# BSU_Sensing.net
KiCad netlist of a schematic drawn in Altium Designer
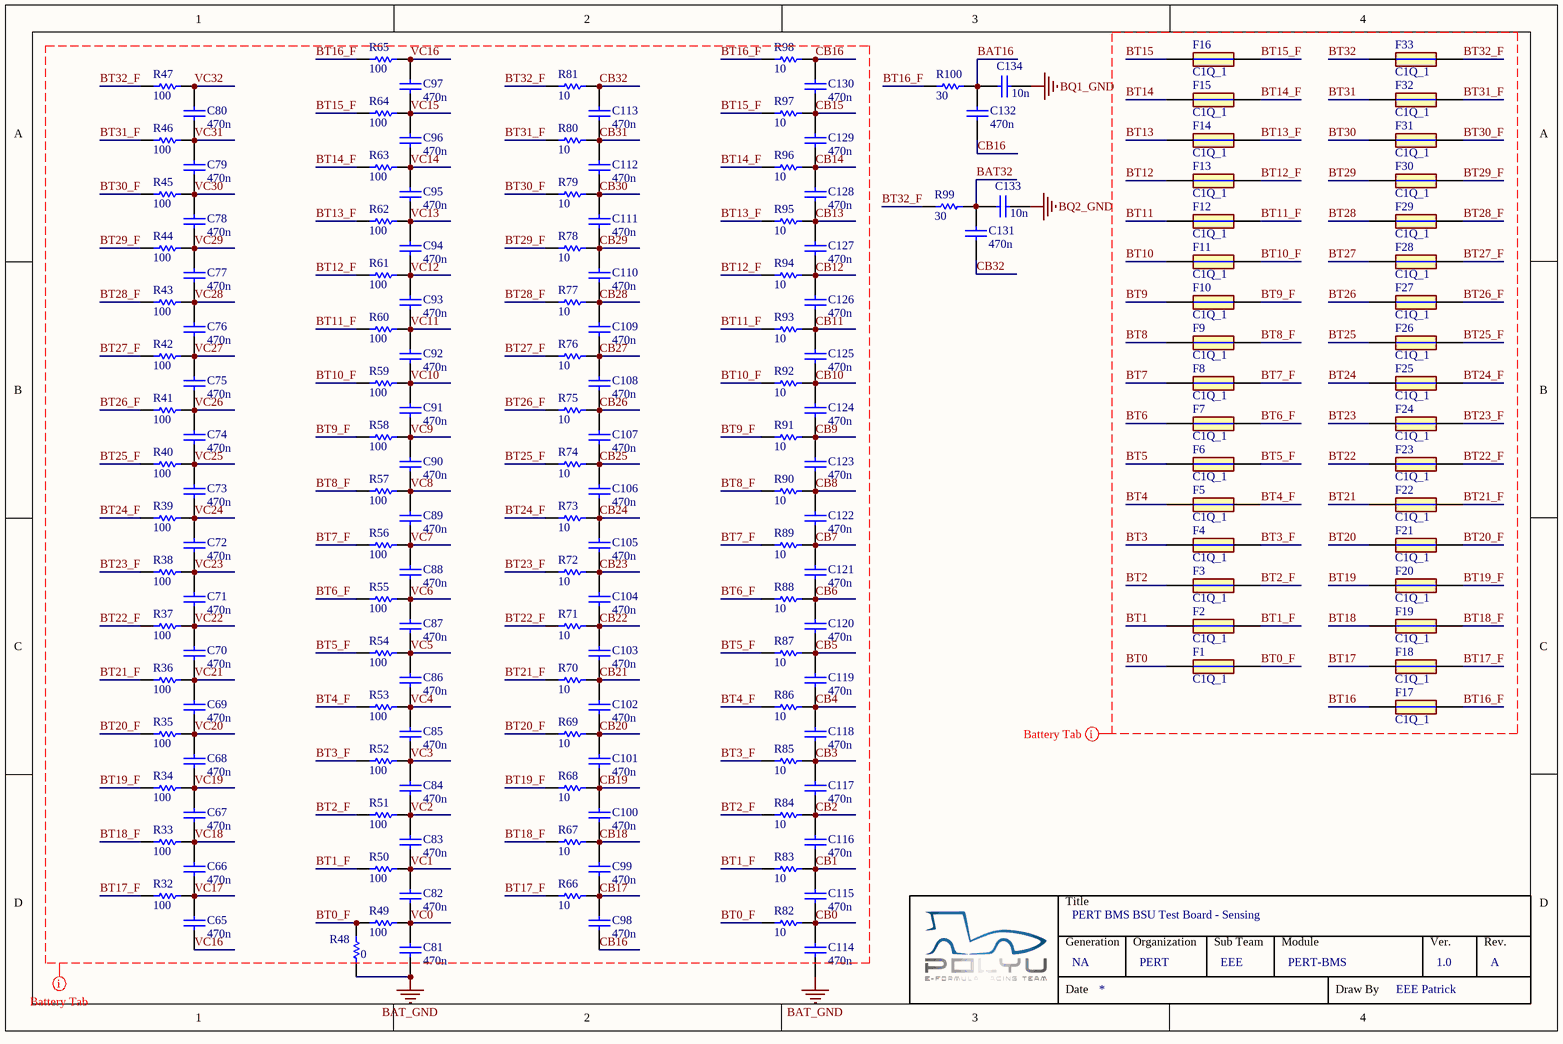
[diagram p0: BSU_Sensing.SchDoc]

(export (version "E")
  (design (tool "Eeschema 10.0.6"))
  (components
    (comp (ref "C65")
      (value "470n")
      (footprint "0603_SMD_C")
      (description "0603 SMD Capacitor")
      (libsource (lib "BMS_ShareComponentLibrary") (part "0603_SMD_Capacitor"))
    )
    (comp (ref "C66")
      (value "470n")
      (footprint "0603_SMD_C")
      (description "0603 SMD Capacitor")
      (libsource (lib "BMS_ShareComponentLibrary") (part "0603_SMD_Capacitor"))
    )
    (comp (ref "C67")
      (value "470n")
      (footprint "0603_SMD_C")
      (description "0603 SMD Capacitor")
      (libsource (lib "BMS_ShareComponentLibrary") (part "0603_SMD_Capacitor"))
    )
    (comp (ref "C68")
      (value "470n")
      (footprint "0603_SMD_C")
      (description "0603 SMD Capacitor")
      (libsource (lib "BMS_ShareComponentLibrary") (part "0603_SMD_Capacitor"))
    )
    (comp (ref "C69")
      (value "470n")
      (footprint "0603_SMD_C")
      (description "0603 SMD Capacitor")
      (libsource (lib "BMS_ShareComponentLibrary") (part "0603_SMD_Capacitor"))
    )
    (comp (ref "C70")
      (value "470n")
      (footprint "0603_SMD_C")
      (description "0603 SMD Capacitor")
      (libsource (lib "BMS_ShareComponentLibrary") (part "0603_SMD_Capacitor"))
    )
    (comp (ref "C71")
      (value "470n")
      (footprint "0603_SMD_C")
      (description "0603 SMD Capacitor")
      (libsource (lib "BMS_ShareComponentLibrary") (part "0603_SMD_Capacitor"))
    )
    (comp (ref "C72")
      (value "470n")
      (footprint "0603_SMD_C")
      (description "0603 SMD Capacitor")
      (libsource (lib "BMS_ShareComponentLibrary") (part "0603_SMD_Capacitor"))
    )
    (comp (ref "C73")
      (value "470n")
      (footprint "0603_SMD_C")
      (description "0603 SMD Capacitor")
      (libsource (lib "BMS_ShareComponentLibrary") (part "0603_SMD_Capacitor"))
    )
    (comp (ref "C74")
      (value "470n")
      (footprint "0603_SMD_C")
      (description "0603 SMD Capacitor")
      (libsource (lib "BMS_ShareComponentLibrary") (part "0603_SMD_Capacitor"))
    )
    (comp (ref "C75")
      (value "470n")
      (footprint "0603_SMD_C")
      (description "0603 SMD Capacitor")
      (libsource (lib "BMS_ShareComponentLibrary") (part "0603_SMD_Capacitor"))
    )
    (comp (ref "C76")
      (value "470n")
      (footprint "0603_SMD_C")
      (description "0603 SMD Capacitor")
      (libsource (lib "BMS_ShareComponentLibrary") (part "0603_SMD_Capacitor"))
    )
    (comp (ref "C77")
      (value "470n")
      (footprint "0603_SMD_C")
      (description "0603 SMD Capacitor")
      (libsource (lib "BMS_ShareComponentLibrary") (part "0603_SMD_Capacitor"))
    )
    (comp (ref "C78")
      (value "470n")
      (footprint "0603_SMD_C")
      (description "0603 SMD Capacitor")
      (libsource (lib "BMS_ShareComponentLibrary") (part "0603_SMD_Capacitor"))
    )
    (comp (ref "C79")
      (value "470n")
      (footprint "0603_SMD_C")
      (description "0603 SMD Capacitor")
      (libsource (lib "BMS_ShareComponentLibrary") (part "0603_SMD_Capacitor"))
    )
    (comp (ref "C80")
      (value "470n")
      (footprint "0603_SMD_C")
      (description "0603 SMD Capacitor")
      (libsource (lib "BMS_ShareComponentLibrary") (part "0603_SMD_Capacitor"))
    )
    (comp (ref "C81")
      (value "470n")
      (footprint "0603_SMD_C")
      (description "0603 SMD Capacitor")
      (libsource (lib "BMS_ShareComponentLibrary") (part "0603_SMD_Capacitor"))
    )
    (comp (ref "C82")
      (value "470n")
      (footprint "0603_SMD_C")
      (description "0603 SMD Capacitor")
      (libsource (lib "BMS_ShareComponentLibrary") (part "0603_SMD_Capacitor"))
    )
    (comp (ref "C83")
      (value "470n")
      (footprint "0603_SMD_C")
      (description "0603 SMD Capacitor")
      (libsource (lib "BMS_ShareComponentLibrary") (part "0603_SMD_Capacitor"))
    )
    (comp (ref "C84")
      (value "470n")
      (footprint "0603_SMD_C")
      (description "0603 SMD Capacitor")
      (libsource (lib "BMS_ShareComponentLibrary") (part "0603_SMD_Capacitor"))
    )
    (comp (ref "C85")
      (value "470n")
      (footprint "0603_SMD_C")
      (description "0603 SMD Capacitor")
      (libsource (lib "BMS_ShareComponentLibrary") (part "0603_SMD_Capacitor"))
    )
    (comp (ref "C86")
      (value "470n")
      (footprint "0603_SMD_C")
      (description "0603 SMD Capacitor")
      (libsource (lib "BMS_ShareComponentLibrary") (part "0603_SMD_Capacitor"))
    )
    (comp (ref "C87")
      (value "470n")
      (footprint "0603_SMD_C")
      (description "0603 SMD Capacitor")
      (libsource (lib "BMS_ShareComponentLibrary") (part "0603_SMD_Capacitor"))
    )
    (comp (ref "C88")
      (value "470n")
      (footprint "0603_SMD_C")
      (description "0603 SMD Capacitor")
      (libsource (lib "BMS_ShareComponentLibrary") (part "0603_SMD_Capacitor"))
    )
    (comp (ref "C89")
      (value "470n")
      (footprint "0603_SMD_C")
      (description "0603 SMD Capacitor")
      (libsource (lib "BMS_ShareComponentLibrary") (part "0603_SMD_Capacitor"))
    )
    (comp (ref "C90")
      (value "470n")
      (footprint "0603_SMD_C")
      (description "0603 SMD Capacitor")
      (libsource (lib "BMS_ShareComponentLibrary") (part "0603_SMD_Capacitor"))
    )
    (comp (ref "C91")
      (value "470n")
      (footprint "0603_SMD_C")
      (description "0603 SMD Capacitor")
      (libsource (lib "BMS_ShareComponentLibrary") (part "0603_SMD_Capacitor"))
    )
    (comp (ref "C92")
      (value "470n")
      (footprint "0603_SMD_C")
      (description "0603 SMD Capacitor")
      (libsource (lib "BMS_ShareComponentLibrary") (part "0603_SMD_Capacitor"))
    )
    (comp (ref "C93")
      (value "470n")
      (footprint "0603_SMD_C")
      (description "0603 SMD Capacitor")
      (libsource (lib "BMS_ShareComponentLibrary") (part "0603_SMD_Capacitor"))
    )
    (comp (ref "C94")
      (value "470n")
      (footprint "0603_SMD_C")
      (description "0603 SMD Capacitor")
      (libsource (lib "BMS_ShareComponentLibrary") (part "0603_SMD_Capacitor"))
    )
    (comp (ref "C95")
      (value "470n")
      (footprint "0603_SMD_C")
      (description "0603 SMD Capacitor")
      (libsource (lib "BMS_ShareComponentLibrary") (part "0603_SMD_Capacitor"))
    )
    (comp (ref "C96")
      (value "470n")
      (footprint "0603_SMD_C")
      (description "0603 SMD Capacitor")
      (libsource (lib "BMS_ShareComponentLibrary") (part "0603_SMD_Capacitor"))
    )
    (comp (ref "C97")
      (value "470n")
      (footprint "0603_SMD_C")
      (description "0603 SMD Capacitor")
      (libsource (lib "BMS_ShareComponentLibrary") (part "0603_SMD_Capacitor"))
    )
    (comp (ref "C98")
      (value "470n")
      (footprint "0603_SMD_C")
      (description "0603 SMD Capacitor")
      (libsource (lib "BMS_ShareComponentLibrary") (part "0603_SMD_Capacitor"))
    )
    (comp (ref "C99")
      (value "470n")
      (footprint "0603_SMD_C")
      (description "0603 SMD Capacitor")
      (libsource (lib "BMS_ShareComponentLibrary") (part "0603_SMD_Capacitor"))
    )
    (comp (ref "C100")
      (value "470n")
      (footprint "0603_SMD_C")
      (description "0603 SMD Capacitor")
      (libsource (lib "BMS_ShareComponentLibrary") (part "0603_SMD_Capacitor"))
    )
    (comp (ref "C101")
      (value "470n")
      (footprint "0603_SMD_C")
      (description "0603 SMD Capacitor")
      (libsource (lib "BMS_ShareComponentLibrary") (part "0603_SMD_Capacitor"))
    )
    (comp (ref "C102")
      (value "470n")
      (footprint "0603_SMD_C")
      (description "0603 SMD Capacitor")
      (libsource (lib "BMS_ShareComponentLibrary") (part "0603_SMD_Capacitor"))
    )
    (comp (ref "C103")
      (value "470n")
      (footprint "0603_SMD_C")
      (description "0603 SMD Capacitor")
      (libsource (lib "BMS_ShareComponentLibrary") (part "0603_SMD_Capacitor"))
    )
    (comp (ref "C104")
      (value "470n")
      (footprint "0603_SMD_C")
      (description "0603 SMD Capacitor")
      (libsource (lib "BMS_ShareComponentLibrary") (part "0603_SMD_Capacitor"))
    )
    (comp (ref "C105")
      (value "470n")
      (footprint "0603_SMD_C")
      (description "0603 SMD Capacitor")
      (libsource (lib "BMS_ShareComponentLibrary") (part "0603_SMD_Capacitor"))
    )
    (comp (ref "C106")
      (value "470n")
      (footprint "0603_SMD_C")
      (description "0603 SMD Capacitor")
      (libsource (lib "BMS_ShareComponentLibrary") (part "0603_SMD_Capacitor"))
    )
    (comp (ref "C107")
      (value "470n")
      (footprint "0603_SMD_C")
      (description "0603 SMD Capacitor")
      (libsource (lib "BMS_ShareComponentLibrary") (part "0603_SMD_Capacitor"))
    )
    (comp (ref "C108")
      (value "470n")
      (footprint "0603_SMD_C")
      (description "0603 SMD Capacitor")
      (libsource (lib "BMS_ShareComponentLibrary") (part "0603_SMD_Capacitor"))
    )
    (comp (ref "C109")
      (value "470n")
      (footprint "0603_SMD_C")
      (description "0603 SMD Capacitor")
      (libsource (lib "BMS_ShareComponentLibrary") (part "0603_SMD_Capacitor"))
    )
    (comp (ref "C110")
      (value "470n")
      (footprint "0603_SMD_C")
      (description "0603 SMD Capacitor")
      (libsource (lib "BMS_ShareComponentLibrary") (part "0603_SMD_Capacitor"))
    )
    (comp (ref "C111")
      (value "470n")
      (footprint "0603_SMD_C")
      (description "0603 SMD Capacitor")
      (libsource (lib "BMS_ShareComponentLibrary") (part "0603_SMD_Capacitor"))
    )
    (comp (ref "C112")
      (value "470n")
      (footprint "0603_SMD_C")
      (description "0603 SMD Capacitor")
      (libsource (lib "BMS_ShareComponentLibrary") (part "0603_SMD_Capacitor"))
    )
    (comp (ref "C113")
      (value "470n")
      (footprint "0603_SMD_C")
      (description "0603 SMD Capacitor")
      (libsource (lib "BMS_ShareComponentLibrary") (part "0603_SMD_Capacitor"))
    )
    (comp (ref "C114")
      (value "470n")
      (footprint "0603_SMD_C")
      (description "0603 SMD Capacitor")
      (libsource (lib "BMS_ShareComponentLibrary") (part "0603_SMD_Capacitor"))
    )
    (comp (ref "C115")
      (value "470n")
      (footprint "0603_SMD_C")
      (description "0603 SMD Capacitor")
      (libsource (lib "BMS_ShareComponentLibrary") (part "0603_SMD_Capacitor"))
    )
    (comp (ref "C116")
      (value "470n")
      (footprint "0603_SMD_C")
      (description "0603 SMD Capacitor")
      (libsource (lib "BMS_ShareComponentLibrary") (part "0603_SMD_Capacitor"))
    )
    (comp (ref "C117")
      (value "470n")
      (footprint "0603_SMD_C")
      (description "0603 SMD Capacitor")
      (libsource (lib "BMS_ShareComponentLibrary") (part "0603_SMD_Capacitor"))
    )
    (comp (ref "C118")
      (value "470n")
      (footprint "0603_SMD_C")
      (description "0603 SMD Capacitor")
      (libsource (lib "BMS_ShareComponentLibrary") (part "0603_SMD_Capacitor"))
    )
    (comp (ref "C119")
      (value "470n")
      (footprint "0603_SMD_C")
      (description "0603 SMD Capacitor")
      (libsource (lib "BMS_ShareComponentLibrary") (part "0603_SMD_Capacitor"))
    )
    (comp (ref "C120")
      (value "470n")
      (footprint "0603_SMD_C")
      (description "0603 SMD Capacitor")
      (libsource (lib "BMS_ShareComponentLibrary") (part "0603_SMD_Capacitor"))
    )
    (comp (ref "C121")
      (value "470n")
      (footprint "0603_SMD_C")
      (description "0603 SMD Capacitor")
      (libsource (lib "BMS_ShareComponentLibrary") (part "0603_SMD_Capacitor"))
    )
    (comp (ref "C122")
      (value "470n")
      (footprint "0603_SMD_C")
      (description "0603 SMD Capacitor")
      (libsource (lib "BMS_ShareComponentLibrary") (part "0603_SMD_Capacitor"))
    )
    (comp (ref "C123")
      (value "470n")
      (footprint "0603_SMD_C")
      (description "0603 SMD Capacitor")
      (libsource (lib "BMS_ShareComponentLibrary") (part "0603_SMD_Capacitor"))
    )
    (comp (ref "C124")
      (value "470n")
      (footprint "0603_SMD_C")
      (description "0603 SMD Capacitor")
      (libsource (lib "BMS_ShareComponentLibrary") (part "0603_SMD_Capacitor"))
    )
    (comp (ref "C125")
      (value "470n")
      (footprint "0603_SMD_C")
      (description "0603 SMD Capacitor")
      (libsource (lib "BMS_ShareComponentLibrary") (part "0603_SMD_Capacitor"))
    )
    (comp (ref "C126")
      (value "470n")
      (footprint "0603_SMD_C")
      (description "0603 SMD Capacitor")
      (libsource (lib "BMS_ShareComponentLibrary") (part "0603_SMD_Capacitor"))
    )
    (comp (ref "C127")
      (value "470n")
      (footprint "0603_SMD_C")
      (description "0603 SMD Capacitor")
      (libsource (lib "BMS_ShareComponentLibrary") (part "0603_SMD_Capacitor"))
    )
    (comp (ref "C128")
      (value "470n")
      (footprint "0603_SMD_C")
      (description "0603 SMD Capacitor")
      (libsource (lib "BMS_ShareComponentLibrary") (part "0603_SMD_Capacitor"))
    )
    (comp (ref "C129")
      (value "470n")
      (footprint "0603_SMD_C")
      (description "0603 SMD Capacitor")
      (libsource (lib "BMS_ShareComponentLibrary") (part "0603_SMD_Capacitor"))
    )
    (comp (ref "C130")
      (value "470n")
      (footprint "0603_SMD_C")
      (description "0603 SMD Capacitor")
      (libsource (lib "BMS_ShareComponentLibrary") (part "0603_SMD_Capacitor"))
    )
    (comp (ref "C131")
      (value "470n")
      (footprint "0805_SMD_C")
      (description "0805 SMD Capacitor")
      (libsource (lib "BMS_ShareComponentLibrary") (part "0805_SMD_Capacitor"))
    )
    (comp (ref "C132")
      (value "470n")
      (footprint "0805_SMD_C")
      (description "0805 SMD Capacitor")
      (libsource (lib "BMS_ShareComponentLibrary") (part "0805_SMD_Capacitor"))
    )
    (comp (ref "C133")
      (value "10n")
      (footprint "0805_SMD_C")
      (description "0805 SMD Capacitor")
      (libsource (lib "BMS_ShareComponentLibrary") (part "0805_SMD_Capacitor"))
    )
    (comp (ref "C134")
      (value "10n")
      (footprint "0805_SMD_C")
      (description "0805 SMD Capacitor")
      (libsource (lib "BMS_ShareComponentLibrary") (part "0805_SMD_Capacitor"))
    )
    (comp (ref "F1")
      (value "C1Q_1")
      (footprint "1206_C1Q")
      (description "T&R")
      (fields
        (field (name "MOUSER PART NUMBER") "530-C1Q1")
        (field (name "MANUFACTURER_PART_NUMBER") "C1Q 1")
      )
      (libsource (lib "BMS_ShareComponentLibrary") (part "Bel Fuse 1206 1A"))
    )
    (comp (ref "F2")
      (value "C1Q_1")
      (footprint "1206_C1Q")
      (description "T&R")
      (fields
        (field (name "MOUSER PART NUMBER") "530-C1Q1")
        (field (name "MANUFACTURER_PART_NUMBER") "C1Q 1")
      )
      (libsource (lib "BMS_ShareComponentLibrary") (part "Bel Fuse 1206 1A"))
    )
    (comp (ref "F3")
      (value "C1Q_1")
      (footprint "1206_C1Q")
      (description "T&R")
      (fields
        (field (name "MOUSER PART NUMBER") "530-C1Q1")
        (field (name "MANUFACTURER_PART_NUMBER") "C1Q 1")
      )
      (libsource (lib "BMS_ShareComponentLibrary") (part "Bel Fuse 1206 1A"))
    )
    (comp (ref "F4")
      (value "C1Q_1")
      (footprint "1206_C1Q")
      (description "T&R")
      (fields
        (field (name "MOUSER PART NUMBER") "530-C1Q1")
        (field (name "MANUFACTURER_PART_NUMBER") "C1Q 1")
      )
      (libsource (lib "BMS_ShareComponentLibrary") (part "Bel Fuse 1206 1A"))
    )
    (comp (ref "F5")
      (value "C1Q_1")
      (footprint "1206_C1Q")
      (description "T&R")
      (fields
        (field (name "MOUSER PART NUMBER") "530-C1Q1")
        (field (name "MANUFACTURER_PART_NUMBER") "C1Q 1")
      )
      (libsource (lib "BMS_ShareComponentLibrary") (part "Bel Fuse 1206 1A"))
    )
    (comp (ref "F6")
      (value "C1Q_1")
      (footprint "1206_C1Q")
      (description "T&R")
      (fields
        (field (name "MOUSER PART NUMBER") "530-C1Q1")
        (field (name "MANUFACTURER_PART_NUMBER") "C1Q 1")
      )
      (libsource (lib "BMS_ShareComponentLibrary") (part "Bel Fuse 1206 1A"))
    )
    (comp (ref "F7")
      (value "C1Q_1")
      (footprint "1206_C1Q")
      (description "T&R")
      (fields
        (field (name "MOUSER PART NUMBER") "530-C1Q1")
        (field (name "MANUFACTURER_PART_NUMBER") "C1Q 1")
      )
      (libsource (lib "BMS_ShareComponentLibrary") (part "Bel Fuse 1206 1A"))
    )
    (comp (ref "F8")
      (value "C1Q_1")
      (footprint "1206_C1Q")
      (description "T&R")
      (fields
        (field (name "MOUSER PART NUMBER") "530-C1Q1")
        (field (name "MANUFACTURER_PART_NUMBER") "C1Q 1")
      )
      (libsource (lib "BMS_ShareComponentLibrary") (part "Bel Fuse 1206 1A"))
    )
    (comp (ref "F9")
      (value "C1Q_1")
      (footprint "1206_C1Q")
      (description "T&R")
      (fields
        (field (name "MOUSER PART NUMBER") "530-C1Q1")
        (field (name "MANUFACTURER_PART_NUMBER") "C1Q 1")
      )
      (libsource (lib "BMS_ShareComponentLibrary") (part "Bel Fuse 1206 1A"))
    )
    (comp (ref "F10")
      (value "C1Q_1")
      (footprint "1206_C1Q")
      (description "T&R")
      (fields
        (field (name "MOUSER PART NUMBER") "530-C1Q1")
        (field (name "MANUFACTURER_PART_NUMBER") "C1Q 1")
      )
      (libsource (lib "BMS_ShareComponentLibrary") (part "Bel Fuse 1206 1A"))
    )
    (comp (ref "F11")
      (value "C1Q_1")
      (footprint "1206_C1Q")
      (description "T&R")
      (fields
        (field (name "MOUSER PART NUMBER") "530-C1Q1")
        (field (name "MANUFACTURER_PART_NUMBER") "C1Q 1")
      )
      (libsource (lib "BMS_ShareComponentLibrary") (part "Bel Fuse 1206 1A"))
    )
    (comp (ref "F12")
      (value "C1Q_1")
      (footprint "1206_C1Q")
      (description "T&R")
      (fields
        (field (name "MOUSER PART NUMBER") "530-C1Q1")
        (field (name "MANUFACTURER_PART_NUMBER") "C1Q 1")
      )
      (libsource (lib "BMS_ShareComponentLibrary") (part "Bel Fuse 1206 1A"))
    )
    (comp (ref "F13")
      (value "C1Q_1")
      (footprint "1206_C1Q")
      (description "T&R")
      (fields
        (field (name "MOUSER PART NUMBER") "530-C1Q1")
        (field (name "MANUFACTURER_PART_NUMBER") "C1Q 1")
      )
      (libsource (lib "BMS_ShareComponentLibrary") (part "Bel Fuse 1206 1A"))
    )
    (comp (ref "F14")
      (value "C1Q_1")
      (footprint "1206_C1Q")
      (description "T&R")
      (fields
        (field (name "MOUSER PART NUMBER") "530-C1Q1")
        (field (name "MANUFACTURER_PART_NUMBER") "C1Q 1")
      )
      (libsource (lib "BMS_ShareComponentLibrary") (part "Bel Fuse 1206 1A"))
    )
    (comp (ref "F15")
      (value "C1Q_1")
      (footprint "1206_C1Q")
      (description "T&R")
      (fields
        (field (name "MOUSER PART NUMBER") "530-C1Q1")
        (field (name "MANUFACTURER_PART_NUMBER") "C1Q 1")
      )
      (libsource (lib "BMS_ShareComponentLibrary") (part "Bel Fuse 1206 1A"))
    )
    (comp (ref "F16")
      (value "C1Q_1")
      (footprint "1206_C1Q")
      (description "T&R")
      (fields
        (field (name "MOUSER PART NUMBER") "530-C1Q1")
        (field (name "MANUFACTURER_PART_NUMBER") "C1Q 1")
      )
      (libsource (lib "BMS_ShareComponentLibrary") (part "Bel Fuse 1206 1A"))
    )
    (comp (ref "F17")
      (value "C1Q_1")
      (footprint "1206_C1Q")
      (description "T&R")
      (fields
        (field (name "MOUSER PART NUMBER") "530-C1Q1")
        (field (name "MANUFACTURER_PART_NUMBER") "C1Q 1")
      )
      (libsource (lib "BMS_ShareComponentLibrary") (part "Bel Fuse 1206 1A"))
    )
    (comp (ref "F18")
      (value "C1Q_1")
      (footprint "1206_C1Q")
      (description "T&R")
      (fields
        (field (name "MOUSER PART NUMBER") "530-C1Q1")
        (field (name "MANUFACTURER_PART_NUMBER") "C1Q 1")
      )
      (libsource (lib "BMS_ShareComponentLibrary") (part "Bel Fuse 1206 1A"))
    )
    (comp (ref "F19")
      (value "C1Q_1")
      (footprint "1206_C1Q")
      (description "T&R")
      (fields
        (field (name "MOUSER PART NUMBER") "530-C1Q1")
        (field (name "MANUFACTURER_PART_NUMBER") "C1Q 1")
      )
      (libsource (lib "BMS_ShareComponentLibrary") (part "Bel Fuse 1206 1A"))
    )
    (comp (ref "F20")
      (value "C1Q_1")
      (footprint "1206_C1Q")
      (description "T&R")
      (fields
        (field (name "MOUSER PART NUMBER") "530-C1Q1")
        (field (name "MANUFACTURER_PART_NUMBER") "C1Q 1")
      )
      (libsource (lib "BMS_ShareComponentLibrary") (part "Bel Fuse 1206 1A"))
    )
    (comp (ref "F21")
      (value "C1Q_1")
      (footprint "1206_C1Q")
      (description "T&R")
      (fields
        (field (name "MOUSER PART NUMBER") "530-C1Q1")
        (field (name "MANUFACTURER_PART_NUMBER") "C1Q 1")
      )
      (libsource (lib "BMS_ShareComponentLibrary") (part "Bel Fuse 1206 1A"))
    )
    (comp (ref "F22")
      (value "C1Q_1")
      (footprint "1206_C1Q")
      (description "T&R")
      (fields
        (field (name "MOUSER PART NUMBER") "530-C1Q1")
        (field (name "MANUFACTURER_PART_NUMBER") "C1Q 1")
      )
      (libsource (lib "BMS_ShareComponentLibrary") (part "Bel Fuse 1206 1A"))
    )
    (comp (ref "F23")
      (value "C1Q_1")
      (footprint "1206_C1Q")
      (description "T&R")
      (fields
        (field (name "MOUSER PART NUMBER") "530-C1Q1")
        (field (name "MANUFACTURER_PART_NUMBER") "C1Q 1")
      )
      (libsource (lib "BMS_ShareComponentLibrary") (part "Bel Fuse 1206 1A"))
    )
    (comp (ref "F24")
      (value "C1Q_1")
      (footprint "1206_C1Q")
      (description "T&R")
      (fields
        (field (name "MOUSER PART NUMBER") "530-C1Q1")
        (field (name "MANUFACTURER_PART_NUMBER") "C1Q 1")
      )
      (libsource (lib "BMS_ShareComponentLibrary") (part "Bel Fuse 1206 1A"))
    )
    (comp (ref "F25")
      (value "C1Q_1")
      (footprint "1206_C1Q")
      (description "T&R")
      (fields
        (field (name "MOUSER PART NUMBER") "530-C1Q1")
        (field (name "MANUFACTURER_PART_NUMBER") "C1Q 1")
      )
      (libsource (lib "BMS_ShareComponentLibrary") (part "Bel Fuse 1206 1A"))
    )
    (comp (ref "F26")
      (value "C1Q_1")
      (footprint "1206_C1Q")
      (description "T&R")
      (fields
        (field (name "MOUSER PART NUMBER") "530-C1Q1")
        (field (name "MANUFACTURER_PART_NUMBER") "C1Q 1")
      )
      (libsource (lib "BMS_ShareComponentLibrary") (part "Bel Fuse 1206 1A"))
    )
    (comp (ref "F27")
      (value "C1Q_1")
      (footprint "1206_C1Q")
      (description "T&R")
      (fields
        (field (name "MOUSER PART NUMBER") "530-C1Q1")
        (field (name "MANUFACTURER_PART_NUMBER") "C1Q 1")
      )
      (libsource (lib "BMS_ShareComponentLibrary") (part "Bel Fuse 1206 1A"))
    )
    (comp (ref "F28")
      (value "C1Q_1")
      (footprint "1206_C1Q")
      (description "T&R")
      (fields
        (field (name "MOUSER PART NUMBER") "530-C1Q1")
        (field (name "MANUFACTURER_PART_NUMBER") "C1Q 1")
      )
      (libsource (lib "BMS_ShareComponentLibrary") (part "Bel Fuse 1206 1A"))
    )
    (comp (ref "F29")
      (value "C1Q_1")
      (footprint "1206_C1Q")
      (description "T&R")
      (fields
        (field (name "MOUSER PART NUMBER") "530-C1Q1")
        (field (name "MANUFACTURER_PART_NUMBER") "C1Q 1")
      )
      (libsource (lib "BMS_ShareComponentLibrary") (part "Bel Fuse 1206 1A"))
    )
    (comp (ref "F30")
      (value "C1Q_1")
      (footprint "1206_C1Q")
      (description "T&R")
      (fields
        (field (name "MOUSER PART NUMBER") "530-C1Q1")
        (field (name "MANUFACTURER_PART_NUMBER") "C1Q 1")
      )
      (libsource (lib "BMS_ShareComponentLibrary") (part "Bel Fuse 1206 1A"))
    )
    (comp (ref "F31")
      (value "C1Q_1")
      (footprint "1206_C1Q")
      (description "T&R")
      (fields
        (field (name "MOUSER PART NUMBER") "530-C1Q1")
        (field (name "MANUFACTURER_PART_NUMBER") "C1Q 1")
      )
      (libsource (lib "BMS_ShareComponentLibrary") (part "Bel Fuse 1206 1A"))
    )
    (comp (ref "F32")
      (value "C1Q_1")
      (footprint "1206_C1Q")
      (description "T&R")
      (fields
        (field (name "MOUSER PART NUMBER") "530-C1Q1")
        (field (name "MANUFACTURER_PART_NUMBER") "C1Q 1")
      )
      (libsource (lib "BMS_ShareComponentLibrary") (part "Bel Fuse 1206 1A"))
    )
    (comp (ref "F33")
      (value "C1Q_1")
      (footprint "1206_C1Q")
      (description "T&R")
      (fields
        (field (name "MOUSER PART NUMBER") "530-C1Q1")
        (field (name "MANUFACTURER_PART_NUMBER") "C1Q 1")
      )
      (libsource (lib "BMS_ShareComponentLibrary") (part "Bel Fuse 1206 1A"))
    )
    (comp (ref "R32")
      (value "100")
      (footprint "0603_SMD_R")
      (description "0603 SMD Resistor")
      (libsource (lib "BMS_ShareComponentLibrary") (part "0603_SMD_Resistor"))
    )
    (comp (ref "R33")
      (value "100")
      (footprint "0603_SMD_R")
      (description "0603 SMD Resistor")
      (libsource (lib "BMS_ShareComponentLibrary") (part "0603_SMD_Resistor"))
    )
    (comp (ref "R34")
      (value "100")
      (footprint "0603_SMD_R")
      (description "0603 SMD Resistor")
      (libsource (lib "BMS_ShareComponentLibrary") (part "0603_SMD_Resistor"))
    )
    (comp (ref "R35")
      (value "100")
      (footprint "0603_SMD_R")
      (description "0603 SMD Resistor")
      (libsource (lib "BMS_ShareComponentLibrary") (part "0603_SMD_Resistor"))
    )
    (comp (ref "R36")
      (value "100")
      (footprint "0603_SMD_R")
      (description "0603 SMD Resistor")
      (libsource (lib "BMS_ShareComponentLibrary") (part "0603_SMD_Resistor"))
    )
    (comp (ref "R37")
      (value "100")
      (footprint "0603_SMD_R")
      (description "0603 SMD Resistor")
      (libsource (lib "BMS_ShareComponentLibrary") (part "0603_SMD_Resistor"))
    )
    (comp (ref "R38")
      (value "100")
      (footprint "0603_SMD_R")
      (description "0603 SMD Resistor")
      (libsource (lib "BMS_ShareComponentLibrary") (part "0603_SMD_Resistor"))
    )
    (comp (ref "R39")
      (value "100")
      (footprint "0603_SMD_R")
      (description "0603 SMD Resistor")
      (libsource (lib "BMS_ShareComponentLibrary") (part "0603_SMD_Resistor"))
    )
    (comp (ref "R40")
      (value "100")
      (footprint "0603_SMD_R")
      (description "0603 SMD Resistor")
      (libsource (lib "BMS_ShareComponentLibrary") (part "0603_SMD_Resistor"))
    )
    (comp (ref "R41")
      (value "100")
      (footprint "0603_SMD_R")
      (description "0603 SMD Resistor")
      (libsource (lib "BMS_ShareComponentLibrary") (part "0603_SMD_Resistor"))
    )
    (comp (ref "R42")
      (value "100")
      (footprint "0603_SMD_R")
      (description "0603 SMD Resistor")
      (libsource (lib "BMS_ShareComponentLibrary") (part "0603_SMD_Resistor"))
    )
    (comp (ref "R43")
      (value "100")
      (footprint "0603_SMD_R")
      (description "0603 SMD Resistor")
      (libsource (lib "BMS_ShareComponentLibrary") (part "0603_SMD_Resistor"))
    )
    (comp (ref "R44")
      (value "100")
      (footprint "0603_SMD_R")
      (description "0603 SMD Resistor")
      (libsource (lib "BMS_ShareComponentLibrary") (part "0603_SMD_Resistor"))
    )
    (comp (ref "R45")
      (value "100")
      (footprint "0603_SMD_R")
      (description "0603 SMD Resistor")
      (libsource (lib "BMS_ShareComponentLibrary") (part "0603_SMD_Resistor"))
    )
    (comp (ref "R46")
      (value "100")
      (footprint "0603_SMD_R")
      (description "0603 SMD Resistor")
      (libsource (lib "BMS_ShareComponentLibrary") (part "0603_SMD_Resistor"))
    )
    (comp (ref "R47")
      (value "100")
      (footprint "0603_SMD_R")
      (description "0603 SMD Resistor")
      (libsource (lib "BMS_ShareComponentLibrary") (part "0603_SMD_Resistor"))
    )
    (comp (ref "R48")
      (value "0")
      (footprint "1210_SMD_R")
      (description "1210 SMD Resistor")
      (libsource (lib "BMS_ShareComponentLibrary") (part "1210_SMD_Resistor"))
    )
    (comp (ref "R49")
      (value "100")
      (footprint "0603_SMD_R")
      (description "0603 SMD Resistor")
      (libsource (lib "BMS_ShareComponentLibrary") (part "0603_SMD_Resistor"))
    )
    (comp (ref "R50")
      (value "100")
      (footprint "0603_SMD_R")
      (description "0603 SMD Resistor")
      (libsource (lib "BMS_ShareComponentLibrary") (part "0603_SMD_Resistor"))
    )
    (comp (ref "R51")
      (value "100")
      (footprint "0603_SMD_R")
      (description "0603 SMD Resistor")
      (libsource (lib "BMS_ShareComponentLibrary") (part "0603_SMD_Resistor"))
    )
    (comp (ref "R52")
      (value "100")
      (footprint "0603_SMD_R")
      (description "0603 SMD Resistor")
      (libsource (lib "BMS_ShareComponentLibrary") (part "0603_SMD_Resistor"))
    )
    (comp (ref "R53")
      (value "100")
      (footprint "0603_SMD_R")
      (description "0603 SMD Resistor")
      (libsource (lib "BMS_ShareComponentLibrary") (part "0603_SMD_Resistor"))
    )
    (comp (ref "R54")
      (value "100")
      (footprint "0603_SMD_R")
      (description "0603 SMD Resistor")
      (libsource (lib "BMS_ShareComponentLibrary") (part "0603_SMD_Resistor"))
    )
    (comp (ref "R55")
      (value "100")
      (footprint "0603_SMD_R")
      (description "0603 SMD Resistor")
      (libsource (lib "BMS_ShareComponentLibrary") (part "0603_SMD_Resistor"))
    )
    (comp (ref "R56")
      (value "100")
      (footprint "0603_SMD_R")
      (description "0603 SMD Resistor")
      (libsource (lib "BMS_ShareComponentLibrary") (part "0603_SMD_Resistor"))
    )
    (comp (ref "R57")
      (value "100")
      (footprint "0603_SMD_R")
      (description "0603 SMD Resistor")
      (libsource (lib "BMS_ShareComponentLibrary") (part "0603_SMD_Resistor"))
    )
    (comp (ref "R58")
      (value "100")
      (footprint "0603_SMD_R")
      (description "0603 SMD Resistor")
      (libsource (lib "BMS_ShareComponentLibrary") (part "0603_SMD_Resistor"))
    )
    (comp (ref "R59")
      (value "100")
      (footprint "0603_SMD_R")
      (description "0603 SMD Resistor")
      (libsource (lib "BMS_ShareComponentLibrary") (part "0603_SMD_Resistor"))
    )
    (comp (ref "R60")
      (value "100")
      (footprint "0603_SMD_R")
      (description "0603 SMD Resistor")
      (libsource (lib "BMS_ShareComponentLibrary") (part "0603_SMD_Resistor"))
    )
    (comp (ref "R61")
      (value "100")
      (footprint "0603_SMD_R")
      (description "0603 SMD Resistor")
      (libsource (lib "BMS_ShareComponentLibrary") (part "0603_SMD_Resistor"))
    )
    (comp (ref "R62")
      (value "100")
      (footprint "0603_SMD_R")
      (description "0603 SMD Resistor")
      (libsource (lib "BMS_ShareComponentLibrary") (part "0603_SMD_Resistor"))
    )
    (comp (ref "R63")
      (value "100")
      (footprint "0603_SMD_R")
      (description "0603 SMD Resistor")
      (libsource (lib "BMS_ShareComponentLibrary") (part "0603_SMD_Resistor"))
    )
    (comp (ref "R64")
      (value "100")
      (footprint "0603_SMD_R")
      (description "0603 SMD Resistor")
      (libsource (lib "BMS_ShareComponentLibrary") (part "0603_SMD_Resistor"))
    )
    (comp (ref "R65")
      (value "100")
      (footprint "0603_SMD_R")
      (description "0603 SMD Resistor")
      (libsource (lib "BMS_ShareComponentLibrary") (part "0603_SMD_Resistor"))
    )
    (comp (ref "R66")
      (value "10")
      (footprint "1210_SMD_R")
      (description "1210 SMD Resistor")
      (libsource (lib "BMS_ShareComponentLibrary") (part "1210_SMD_Resistor"))
    )
    (comp (ref "R67")
      (value "10")
      (footprint "1210_SMD_R")
      (description "1210 SMD Resistor")
      (libsource (lib "BMS_ShareComponentLibrary") (part "1210_SMD_Resistor"))
    )
    (comp (ref "R68")
      (value "10")
      (footprint "1210_SMD_R")
      (description "1210 SMD Resistor")
      (libsource (lib "BMS_ShareComponentLibrary") (part "1210_SMD_Resistor"))
    )
    (comp (ref "R69")
      (value "10")
      (footprint "1210_SMD_R")
      (description "1210 SMD Resistor")
      (libsource (lib "BMS_ShareComponentLibrary") (part "1210_SMD_Resistor"))
    )
    (comp (ref "R70")
      (value "10")
      (footprint "1210_SMD_R")
      (description "1210 SMD Resistor")
      (libsource (lib "BMS_ShareComponentLibrary") (part "1210_SMD_Resistor"))
    )
    (comp (ref "R71")
      (value "10")
      (footprint "1210_SMD_R")
      (description "1210 SMD Resistor")
      (libsource (lib "BMS_ShareComponentLibrary") (part "1210_SMD_Resistor"))
    )
    (comp (ref "R72")
      (value "10")
      (footprint "1210_SMD_R")
      (description "1210 SMD Resistor")
      (libsource (lib "BMS_ShareComponentLibrary") (part "1210_SMD_Resistor"))
    )
    (comp (ref "R73")
      (value "10")
      (footprint "1210_SMD_R")
      (description "1210 SMD Resistor")
      (libsource (lib "BMS_ShareComponentLibrary") (part "1210_SMD_Resistor"))
    )
    (comp (ref "R74")
      (value "10")
      (footprint "1210_SMD_R")
      (description "1210 SMD Resistor")
      (libsource (lib "BMS_ShareComponentLibrary") (part "1210_SMD_Resistor"))
    )
    (comp (ref "R75")
      (value "10")
      (footprint "1210_SMD_R")
      (description "1210 SMD Resistor")
      (libsource (lib "BMS_ShareComponentLibrary") (part "1210_SMD_Resistor"))
    )
    (comp (ref "R76")
      (value "10")
      (footprint "1210_SMD_R")
      (description "1210 SMD Resistor")
      (libsource (lib "BMS_ShareComponentLibrary") (part "1210_SMD_Resistor"))
    )
    (comp (ref "R77")
      (value "10")
      (footprint "1210_SMD_R")
      (description "1210 SMD Resistor")
      (libsource (lib "BMS_ShareComponentLibrary") (part "1210_SMD_Resistor"))
    )
    (comp (ref "R78")
      (value "10")
      (footprint "1210_SMD_R")
      (description "1210 SMD Resistor")
      (libsource (lib "BMS_ShareComponentLibrary") (part "1210_SMD_Resistor"))
    )
    (comp (ref "R79")
      (value "10")
      (footprint "1210_SMD_R")
      (description "1210 SMD Resistor")
      (libsource (lib "BMS_ShareComponentLibrary") (part "1210_SMD_Resistor"))
    )
    (comp (ref "R80")
      (value "10")
      (footprint "1210_SMD_R")
      (description "1210 SMD Resistor")
      (libsource (lib "BMS_ShareComponentLibrary") (part "1210_SMD_Resistor"))
    )
    (comp (ref "R81")
      (value "10")
      (footprint "1210_SMD_R")
      (description "1210 SMD Resistor")
      (libsource (lib "BMS_ShareComponentLibrary") (part "1210_SMD_Resistor"))
    )
    (comp (ref "R82")
      (value "10")
      (footprint "1210_SMD_R")
      (description "1210 SMD Resistor")
      (libsource (lib "BMS_ShareComponentLibrary") (part "1210_SMD_Resistor"))
    )
    (comp (ref "R83")
      (value "10")
      (footprint "1210_SMD_R")
      (description "1210 SMD Resistor")
      (libsource (lib "BMS_ShareComponentLibrary") (part "1210_SMD_Resistor"))
    )
    (comp (ref "R84")
      (value "10")
      (footprint "1210_SMD_R")
      (description "1210 SMD Resistor")
      (libsource (lib "BMS_ShareComponentLibrary") (part "1210_SMD_Resistor"))
    )
    (comp (ref "R85")
      (value "10")
      (footprint "1210_SMD_R")
      (description "1210 SMD Resistor")
      (libsource (lib "BMS_ShareComponentLibrary") (part "1210_SMD_Resistor"))
    )
    (comp (ref "R86")
      (value "10")
      (footprint "1210_SMD_R")
      (description "1210 SMD Resistor")
      (libsource (lib "BMS_ShareComponentLibrary") (part "1210_SMD_Resistor"))
    )
    (comp (ref "R87")
      (value "10")
      (footprint "1210_SMD_R")
      (description "1210 SMD Resistor")
      (libsource (lib "BMS_ShareComponentLibrary") (part "1210_SMD_Resistor"))
    )
    (comp (ref "R88")
      (value "10")
      (footprint "1210_SMD_R")
      (description "1210 SMD Resistor")
      (libsource (lib "BMS_ShareComponentLibrary") (part "1210_SMD_Resistor"))
    )
    (comp (ref "R89")
      (value "10")
      (footprint "1210_SMD_R")
      (description "1210 SMD Resistor")
      (libsource (lib "BMS_ShareComponentLibrary") (part "1210_SMD_Resistor"))
    )
    (comp (ref "R90")
      (value "10")
      (footprint "1210_SMD_R")
      (description "1210 SMD Resistor")
      (libsource (lib "BMS_ShareComponentLibrary") (part "1210_SMD_Resistor"))
    )
    (comp (ref "R91")
      (value "10")
      (footprint "1210_SMD_R")
      (description "1210 SMD Resistor")
      (libsource (lib "BMS_ShareComponentLibrary") (part "1210_SMD_Resistor"))
    )
    (comp (ref "R92")
      (value "10")
      (footprint "1210_SMD_R")
      (description "1210 SMD Resistor")
      (libsource (lib "BMS_ShareComponentLibrary") (part "1210_SMD_Resistor"))
    )
    (comp (ref "R93")
      (value "10")
      (footprint "1210_SMD_R")
      (description "1210 SMD Resistor")
      (libsource (lib "BMS_ShareComponentLibrary") (part "1210_SMD_Resistor"))
    )
    (comp (ref "R94")
      (value "10")
      (footprint "1210_SMD_R")
      (description "1210 SMD Resistor")
      (libsource (lib "BMS_ShareComponentLibrary") (part "1210_SMD_Resistor"))
    )
    (comp (ref "R95")
      (value "10")
      (footprint "1210_SMD_R")
      (description "1210 SMD Resistor")
      (libsource (lib "BMS_ShareComponentLibrary") (part "1210_SMD_Resistor"))
    )
    (comp (ref "R96")
      (value "10")
      (footprint "1210_SMD_R")
      (description "1210 SMD Resistor")
      (libsource (lib "BMS_ShareComponentLibrary") (part "1210_SMD_Resistor"))
    )
    (comp (ref "R97")
      (value "10")
      (footprint "1210_SMD_R")
      (description "1210 SMD Resistor")
      (libsource (lib "BMS_ShareComponentLibrary") (part "1210_SMD_Resistor"))
    )
    (comp (ref "R98")
      (value "10")
      (footprint "1210_SMD_R")
      (description "1210 SMD Resistor")
      (libsource (lib "BMS_ShareComponentLibrary") (part "1210_SMD_Resistor"))
    )
    (comp (ref "R99")
      (value "30")
      (footprint "0805_SMD_R")
      (description "0805 SMD Resistor")
      (libsource (lib "BMS_ShareComponentLibrary") (part "0805_SMD_Resistor"))
    )
    (comp (ref "R100")
      (value "30")
      (footprint "0805_SMD_R")
      (description "0805 SMD Resistor")
      (libsource (lib "BMS_ShareComponentLibrary") (part "0805_SMD_Resistor"))
    )
  )
  (nets
    (net (code "1") (name "/BAT16") (class "Default")
      (node (ref "C132") (pin "2") (pinfunction "2_2") (pintype "passive"))
      (node (ref "C134") (pin "2") (pinfunction "2_2") (pintype "passive"))
      (node (ref "R100") (pin "2") (pinfunction "2_2") (pintype "passive"))
    )
    (net (code "2") (name "/BAT32") (class "Default")
      (node (ref "C131") (pin "2") (pinfunction "2_2") (pintype "passive"))
      (node (ref "C133") (pin "2") (pinfunction "2_2") (pintype "passive"))
      (node (ref "R99") (pin "2") (pinfunction "2_2") (pintype "passive"))
    )
    (net (code "3") (name "/BT0") (class "Default")
      (node (ref "F1") (pin "1") (pinfunction "1_1") (pintype "passive"))
    )
    (net (code "4") (name "/BT0_F") (class "Default")
      (node (ref "F1") (pin "2") (pinfunction "2_2") (pintype "passive"))
      (node (ref "R48") (pin "2") (pinfunction "2_2") (pintype "passive"))
      (node (ref "R49") (pin "1") (pinfunction "1_1") (pintype "passive"))
      (node (ref "R82") (pin "1") (pinfunction "1_1") (pintype "passive"))
    )
    (net (code "5") (name "/BT1") (class "Default")
      (node (ref "F2") (pin "1") (pinfunction "1_1") (pintype "passive"))
    )
    (net (code "6") (name "/BT1_F") (class "Default")
      (node (ref "F2") (pin "2") (pinfunction "2_2") (pintype "passive"))
      (node (ref "R50") (pin "1") (pinfunction "1_1") (pintype "passive"))
      (node (ref "R83") (pin "1") (pinfunction "1_1") (pintype "passive"))
    )
    (net (code "7") (name "/BT2") (class "Default")
      (node (ref "F3") (pin "1") (pinfunction "1_1") (pintype "passive"))
    )
    (net (code "8") (name "/BT2_F") (class "Default")
      (node (ref "F3") (pin "2") (pinfunction "2_2") (pintype "passive"))
      (node (ref "R51") (pin "1") (pinfunction "1_1") (pintype "passive"))
      (node (ref "R84") (pin "1") (pinfunction "1_1") (pintype "passive"))
    )
    (net (code "9") (name "/BT3") (class "Default")
      (node (ref "F4") (pin "1") (pinfunction "1_1") (pintype "passive"))
    )
    (net (code "10") (name "/BT3_F") (class "Default")
      (node (ref "F4") (pin "2") (pinfunction "2_2") (pintype "passive"))
      (node (ref "R52") (pin "1") (pinfunction "1_1") (pintype "passive"))
      (node (ref "R85") (pin "1") (pinfunction "1_1") (pintype "passive"))
    )
    (net (code "11") (name "/BT4") (class "Default")
      (node (ref "F5") (pin "1") (pinfunction "1_1") (pintype "passive"))
    )
    (net (code "12") (name "/BT4_F") (class "Default")
      (node (ref "F5") (pin "2") (pinfunction "2_2") (pintype "passive"))
      (node (ref "R53") (pin "1") (pinfunction "1_1") (pintype "passive"))
      (node (ref "R86") (pin "1") (pinfunction "1_1") (pintype "passive"))
    )
    (net (code "13") (name "/BT5") (class "Default")
      (node (ref "F6") (pin "1") (pinfunction "1_1") (pintype "passive"))
    )
    (net (code "14") (name "/BT5_F") (class "Default")
      (node (ref "F6") (pin "2") (pinfunction "2_2") (pintype "passive"))
      (node (ref "R54") (pin "1") (pinfunction "1_1") (pintype "passive"))
      (node (ref "R87") (pin "1") (pinfunction "1_1") (pintype "passive"))
    )
    (net (code "15") (name "/BT6") (class "Default")
      (node (ref "F7") (pin "1") (pinfunction "1_1") (pintype "passive"))
    )
    (net (code "16") (name "/BT6_F") (class "Default")
      (node (ref "F7") (pin "2") (pinfunction "2_2") (pintype "passive"))
      (node (ref "R55") (pin "1") (pinfunction "1_1") (pintype "passive"))
      (node (ref "R88") (pin "1") (pinfunction "1_1") (pintype "passive"))
    )
    (net (code "17") (name "/BT7") (class "Default")
      (node (ref "F8") (pin "1") (pinfunction "1_1") (pintype "passive"))
    )
    (net (code "18") (name "/BT7_F") (class "Default")
      (node (ref "F8") (pin "2") (pinfunction "2_2") (pintype "passive"))
      (node (ref "R56") (pin "1") (pinfunction "1_1") (pintype "passive"))
      (node (ref "R89") (pin "1") (pinfunction "1_1") (pintype "passive"))
    )
    (net (code "19") (name "/BT8") (class "Default")
      (node (ref "F9") (pin "1") (pinfunction "1_1") (pintype "passive"))
    )
    (net (code "20") (name "/BT8_F") (class "Default")
      (node (ref "F9") (pin "2") (pinfunction "2_2") (pintype "passive"))
      (node (ref "R57") (pin "1") (pinfunction "1_1") (pintype "passive"))
      (node (ref "R90") (pin "1") (pinfunction "1_1") (pintype "passive"))
    )
    (net (code "21") (name "/BT9") (class "Default")
      (node (ref "F10") (pin "1") (pinfunction "1_1") (pintype "passive"))
    )
    (net (code "22") (name "/BT9_F") (class "Default")
      (node (ref "F10") (pin "2") (pinfunction "2_2") (pintype "passive"))
      (node (ref "R58") (pin "1") (pinfunction "1_1") (pintype "passive"))
      (node (ref "R91") (pin "1") (pinfunction "1_1") (pintype "passive"))
    )
    (net (code "23") (name "/BT10") (class "Default")
      (node (ref "F11") (pin "1") (pinfunction "1_1") (pintype "passive"))
    )
    (net (code "24") (name "/BT10_F") (class "Default")
      (node (ref "F11") (pin "2") (pinfunction "2_2") (pintype "passive"))
      (node (ref "R59") (pin "1") (pinfunction "1_1") (pintype "passive"))
      (node (ref "R92") (pin "1") (pinfunction "1_1") (pintype "passive"))
    )
    (net (code "25") (name "/BT11") (class "Default")
      (node (ref "F12") (pin "1") (pinfunction "1_1") (pintype "passive"))
    )
    (net (code "26") (name "/BT11_F") (class "Default")
      (node (ref "F12") (pin "2") (pinfunction "2_2") (pintype "passive"))
      (node (ref "R60") (pin "1") (pinfunction "1_1") (pintype "passive"))
      (node (ref "R93") (pin "1") (pinfunction "1_1") (pintype "passive"))
    )
    (net (code "27") (name "/BT12") (class "Default")
      (node (ref "F13") (pin "1") (pinfunction "1_1") (pintype "passive"))
    )
    (net (code "28") (name "/BT12_F") (class "Default")
      (node (ref "F13") (pin "2") (pinfunction "2_2") (pintype "passive"))
      (node (ref "R61") (pin "1") (pinfunction "1_1") (pintype "passive"))
      (node (ref "R94") (pin "1") (pinfunction "1_1") (pintype "passive"))
    )
    (net (code "29") (name "/BT13") (class "Default")
      (node (ref "F14") (pin "1") (pinfunction "1_1") (pintype "passive"))
    )
    (net (code "30") (name "/BT13_F") (class "Default")
      (node (ref "F14") (pin "2") (pinfunction "2_2") (pintype "passive"))
      (node (ref "R62") (pin "1") (pinfunction "1_1") (pintype "passive"))
      (node (ref "R95") (pin "1") (pinfunction "1_1") (pintype "passive"))
    )
    (net (code "31") (name "/BT14") (class "Default")
      (node (ref "F15") (pin "1") (pinfunction "1_1") (pintype "passive"))
    )
    (net (code "32") (name "/BT14_F") (class "Default")
      (node (ref "F15") (pin "2") (pinfunction "2_2") (pintype "passive"))
      (node (ref "R63") (pin "1") (pinfunction "1_1") (pintype "passive"))
      (node (ref "R96") (pin "1") (pinfunction "1_1") (pintype "passive"))
    )
    (net (code "33") (name "/BT15") (class "Default")
      (node (ref "F16") (pin "1") (pinfunction "1_1") (pintype "passive"))
    )
    (net (code "34") (name "/BT15_F") (class "Default")
      (node (ref "F16") (pin "2") (pinfunction "2_2") (pintype "passive"))
      (node (ref "R64") (pin "1") (pinfunction "1_1") (pintype "passive"))
      (node (ref "R97") (pin "1") (pinfunction "1_1") (pintype "passive"))
    )
    (net (code "35") (name "/BT16") (class "Default")
      (node (ref "F17") (pin "1") (pinfunction "1_1") (pintype "passive"))
    )
    (net (code "36") (name "/BT16_F") (class "Default")
      (node (ref "F17") (pin "2") (pinfunction "2_2") (pintype "passive"))
      (node (ref "R100") (pin "1") (pinfunction "1_1") (pintype "passive"))
      (node (ref "R65") (pin "1") (pinfunction "1_1") (pintype "passive"))
      (node (ref "R98") (pin "1") (pinfunction "1_1") (pintype "passive"))
    )
    (net (code "37") (name "/BT17") (class "Default")
      (node (ref "F18") (pin "1") (pinfunction "1_1") (pintype "passive"))
    )
    (net (code "38") (name "/BT17_F") (class "Default")
      (node (ref "F18") (pin "2") (pinfunction "2_2") (pintype "passive"))
      (node (ref "R32") (pin "1") (pinfunction "1_1") (pintype "passive"))
      (node (ref "R66") (pin "1") (pinfunction "1_1") (pintype "passive"))
    )
    (net (code "39") (name "/BT18") (class "Default")
      (node (ref "F19") (pin "1") (pinfunction "1_1") (pintype "passive"))
    )
    (net (code "40") (name "/BT18_F") (class "Default")
      (node (ref "F19") (pin "2") (pinfunction "2_2") (pintype "passive"))
      (node (ref "R33") (pin "1") (pinfunction "1_1") (pintype "passive"))
      (node (ref "R67") (pin "1") (pinfunction "1_1") (pintype "passive"))
    )
    (net (code "41") (name "/BT19") (class "Default")
      (node (ref "F20") (pin "1") (pinfunction "1_1") (pintype "passive"))
    )
    (net (code "42") (name "/BT19_F") (class "Default")
      (node (ref "F20") (pin "2") (pinfunction "2_2") (pintype "passive"))
      (node (ref "R34") (pin "1") (pinfunction "1_1") (pintype "passive"))
      (node (ref "R68") (pin "1") (pinfunction "1_1") (pintype "passive"))
    )
    (net (code "43") (name "/BT20") (class "Default")
      (node (ref "F21") (pin "1") (pinfunction "1_1") (pintype "passive"))
    )
    (net (code "44") (name "/BT20_F") (class "Default")
      (node (ref "F21") (pin "2") (pinfunction "2_2") (pintype "passive"))
      (node (ref "R35") (pin "1") (pinfunction "1_1") (pintype "passive"))
      (node (ref "R69") (pin "1") (pinfunction "1_1") (pintype "passive"))
    )
    (net (code "45") (name "/BT21") (class "Default")
      (node (ref "F22") (pin "1") (pinfunction "1_1") (pintype "passive"))
    )
    (net (code "46") (name "/BT21_F") (class "Default")
      (node (ref "F22") (pin "2") (pinfunction "2_2") (pintype "passive"))
      (node (ref "R36") (pin "1") (pinfunction "1_1") (pintype "passive"))
      (node (ref "R70") (pin "1") (pinfunction "1_1") (pintype "passive"))
    )
    (net (code "47") (name "/BT22") (class "Default")
      (node (ref "F23") (pin "1") (pinfunction "1_1") (pintype "passive"))
    )
    (net (code "48") (name "/BT22_F") (class "Default")
      (node (ref "F23") (pin "2") (pinfunction "2_2") (pintype "passive"))
      (node (ref "R37") (pin "1") (pinfunction "1_1") (pintype "passive"))
      (node (ref "R71") (pin "1") (pinfunction "1_1") (pintype "passive"))
    )
    (net (code "49") (name "/BT23") (class "Default")
      (node (ref "F24") (pin "1") (pinfunction "1_1") (pintype "passive"))
    )
    (net (code "50") (name "/BT23_F") (class "Default")
      (node (ref "F24") (pin "2") (pinfunction "2_2") (pintype "passive"))
      (node (ref "R38") (pin "1") (pinfunction "1_1") (pintype "passive"))
      (node (ref "R72") (pin "1") (pinfunction "1_1") (pintype "passive"))
    )
    (net (code "51") (name "/BT24") (class "Default")
      (node (ref "F25") (pin "1") (pinfunction "1_1") (pintype "passive"))
    )
    (net (code "52") (name "/BT24_F") (class "Default")
      (node (ref "F25") (pin "2") (pinfunction "2_2") (pintype "passive"))
      (node (ref "R39") (pin "1") (pinfunction "1_1") (pintype "passive"))
      (node (ref "R73") (pin "1") (pinfunction "1_1") (pintype "passive"))
    )
    (net (code "53") (name "/BT25") (class "Default")
      (node (ref "F26") (pin "1") (pinfunction "1_1") (pintype "passive"))
    )
    (net (code "54") (name "/BT25_F") (class "Default")
      (node (ref "F26") (pin "2") (pinfunction "2_2") (pintype "passive"))
      (node (ref "R40") (pin "1") (pinfunction "1_1") (pintype "passive"))
      (node (ref "R74") (pin "1") (pinfunction "1_1") (pintype "passive"))
    )
    (net (code "55") (name "/BT26") (class "Default")
      (node (ref "F27") (pin "1") (pinfunction "1_1") (pintype "passive"))
    )
    (net (code "56") (name "/BT26_F") (class "Default")
      (node (ref "F27") (pin "2") (pinfunction "2_2") (pintype "passive"))
      (node (ref "R41") (pin "1") (pinfunction "1_1") (pintype "passive"))
      (node (ref "R75") (pin "1") (pinfunction "1_1") (pintype "passive"))
    )
    (net (code "57") (name "/BT27") (class "Default")
      (node (ref "F28") (pin "1") (pinfunction "1_1") (pintype "passive"))
    )
    (net (code "58") (name "/BT27_F") (class "Default")
      (node (ref "F28") (pin "2") (pinfunction "2_2") (pintype "passive"))
      (node (ref "R42") (pin "1") (pinfunction "1_1") (pintype "passive"))
      (node (ref "R76") (pin "1") (pinfunction "1_1") (pintype "passive"))
    )
    (net (code "59") (name "/BT28") (class "Default")
      (node (ref "F29") (pin "1") (pinfunction "1_1") (pintype "passive"))
    )
    (net (code "60") (name "/BT28_F") (class "Default")
      (node (ref "F29") (pin "2") (pinfunction "2_2") (pintype "passive"))
      (node (ref "R43") (pin "1") (pinfunction "1_1") (pintype "passive"))
      (node (ref "R77") (pin "1") (pinfunction "1_1") (pintype "passive"))
    )
    (net (code "61") (name "/BT29") (class "Default")
      (node (ref "F30") (pin "1") (pinfunction "1_1") (pintype "passive"))
    )
    (net (code "62") (name "/BT29_F") (class "Default")
      (node (ref "F30") (pin "2") (pinfunction "2_2") (pintype "passive"))
      (node (ref "R44") (pin "1") (pinfunction "1_1") (pintype "passive"))
      (node (ref "R78") (pin "1") (pinfunction "1_1") (pintype "passive"))
    )
    (net (code "63") (name "/BT30") (class "Default")
      (node (ref "F31") (pin "1") (pinfunction "1_1") (pintype "passive"))
    )
    (net (code "64") (name "/BT30_F") (class "Default")
      (node (ref "F31") (pin "2") (pinfunction "2_2") (pintype "passive"))
      (node (ref "R45") (pin "1") (pinfunction "1_1") (pintype "passive"))
      (node (ref "R79") (pin "1") (pinfunction "1_1") (pintype "passive"))
    )
    (net (code "65") (name "/BT31") (class "Default")
      (node (ref "F32") (pin "1") (pinfunction "1_1") (pintype "passive"))
    )
    (net (code "66") (name "/BT31_F") (class "Default")
      (node (ref "F32") (pin "2") (pinfunction "2_2") (pintype "passive"))
      (node (ref "R46") (pin "1") (pinfunction "1_1") (pintype "passive"))
      (node (ref "R80") (pin "1") (pinfunction "1_1") (pintype "passive"))
    )
    (net (code "67") (name "/BT32") (class "Default")
      (node (ref "F33") (pin "1") (pinfunction "1_1") (pintype "passive"))
    )
    (net (code "68") (name "/BT32_F") (class "Default")
      (node (ref "F33") (pin "2") (pinfunction "2_2") (pintype "passive"))
      (node (ref "R47") (pin "1") (pinfunction "1_1") (pintype "passive"))
      (node (ref "R81") (pin "1") (pinfunction "1_1") (pintype "passive"))
      (node (ref "R99") (pin "1") (pinfunction "1_1") (pintype "passive"))
    )
    (net (code "69") (name "/CB0") (class "Default")
      (node (ref "C114") (pin "2") (pinfunction "2_2") (pintype "passive"))
      (node (ref "C115") (pin "1") (pinfunction "1_1") (pintype "passive"))
      (node (ref "R82") (pin "2") (pinfunction "2_2") (pintype "passive"))
    )
    (net (code "70") (name "/CB1") (class "Default")
      (node (ref "C115") (pin "2") (pinfunction "2_2") (pintype "passive"))
      (node (ref "C116") (pin "1") (pinfunction "1_1") (pintype "passive"))
      (node (ref "R83") (pin "2") (pinfunction "2_2") (pintype "passive"))
    )
    (net (code "71") (name "/CB2") (class "Default")
      (node (ref "C116") (pin "2") (pinfunction "2_2") (pintype "passive"))
      (node (ref "C117") (pin "1") (pinfunction "1_1") (pintype "passive"))
      (node (ref "R84") (pin "2") (pinfunction "2_2") (pintype "passive"))
    )
    (net (code "72") (name "/CB3") (class "Default")
      (node (ref "C117") (pin "2") (pinfunction "2_2") (pintype "passive"))
      (node (ref "C118") (pin "1") (pinfunction "1_1") (pintype "passive"))
      (node (ref "R85") (pin "2") (pinfunction "2_2") (pintype "passive"))
    )
    (net (code "73") (name "/CB4") (class "Default")
      (node (ref "C118") (pin "2") (pinfunction "2_2") (pintype "passive"))
      (node (ref "C119") (pin "1") (pinfunction "1_1") (pintype "passive"))
      (node (ref "R86") (pin "2") (pinfunction "2_2") (pintype "passive"))
    )
    (net (code "74") (name "/CB5") (class "Default")
      (node (ref "C119") (pin "2") (pinfunction "2_2") (pintype "passive"))
      (node (ref "C120") (pin "1") (pinfunction "1_1") (pintype "passive"))
      (node (ref "R87") (pin "2") (pinfunction "2_2") (pintype "passive"))
    )
    (net (code "75") (name "/CB6") (class "Default")
      (node (ref "C120") (pin "2") (pinfunction "2_2") (pintype "passive"))
      (node (ref "C121") (pin "1") (pinfunction "1_1") (pintype "passive"))
      (node (ref "R88") (pin "2") (pinfunction "2_2") (pintype "passive"))
    )
    (net (code "76") (name "/CB7") (class "Default")
      (node (ref "C121") (pin "2") (pinfunction "2_2") (pintype "passive"))
      (node (ref "C122") (pin "1") (pinfunction "1_1") (pintype "passive"))
      (node (ref "R89") (pin "2") (pinfunction "2_2") (pintype "passive"))
    )
    (net (code "77") (name "/CB8") (class "Default")
      (node (ref "C122") (pin "2") (pinfunction "2_2") (pintype "passive"))
      (node (ref "C123") (pin "1") (pinfunction "1_1") (pintype "passive"))
      (node (ref "R90") (pin "2") (pinfunction "2_2") (pintype "passive"))
    )
    (net (code "78") (name "/CB9") (class "Default")
      (node (ref "C123") (pin "2") (pinfunction "2_2") (pintype "passive"))
      (node (ref "C124") (pin "1") (pinfunction "1_1") (pintype "passive"))
      (node (ref "R91") (pin "2") (pinfunction "2_2") (pintype "passive"))
    )
    (net (code "79") (name "/CB10") (class "Default")
      (node (ref "C124") (pin "2") (pinfunction "2_2") (pintype "passive"))
      (node (ref "C125") (pin "1") (pinfunction "1_1") (pintype "passive"))
      (node (ref "R92") (pin "2") (pinfunction "2_2") (pintype "passive"))
    )
    (net (code "80") (name "/CB11") (class "Default")
      (node (ref "C125") (pin "2") (pinfunction "2_2") (pintype "passive"))
      (node (ref "C126") (pin "1") (pinfunction "1_1") (pintype "passive"))
      (node (ref "R93") (pin "2") (pinfunction "2_2") (pintype "passive"))
    )
    (net (code "81") (name "/CB12") (class "Default")
      (node (ref "C126") (pin "2") (pinfunction "2_2") (pintype "passive"))
      (node (ref "C127") (pin "1") (pinfunction "1_1") (pintype "passive"))
      (node (ref "R94") (pin "2") (pinfunction "2_2") (pintype "passive"))
    )
    (net (code "82") (name "/CB13") (class "Default")
      (node (ref "C127") (pin "2") (pinfunction "2_2") (pintype "passive"))
      (node (ref "C128") (pin "1") (pinfunction "1_1") (pintype "passive"))
      (node (ref "R95") (pin "2") (pinfunction "2_2") (pintype "passive"))
    )
    (net (code "83") (name "/CB14") (class "Default")
      (node (ref "C128") (pin "2") (pinfunction "2_2") (pintype "passive"))
      (node (ref "C129") (pin "1") (pinfunction "1_1") (pintype "passive"))
      (node (ref "R96") (pin "2") (pinfunction "2_2") (pintype "passive"))
    )
    (net (code "84") (name "/CB15") (class "Default")
      (node (ref "C129") (pin "2") (pinfunction "2_2") (pintype "passive"))
      (node (ref "C130") (pin "1") (pinfunction "1_1") (pintype "passive"))
      (node (ref "R97") (pin "2") (pinfunction "2_2") (pintype "passive"))
    )
    (net (code "85") (name "/CB16") (class "Default")
      (node (ref "C130") (pin "2") (pinfunction "2_2") (pintype "passive"))
      (node (ref "C132") (pin "1") (pinfunction "1_1") (pintype "passive"))
      (node (ref "C98") (pin "1") (pinfunction "1_1") (pintype "passive"))
      (node (ref "R98") (pin "2") (pinfunction "2_2") (pintype "passive"))
    )
    (net (code "86") (name "/CB17") (class "Default")
      (node (ref "C98") (pin "2") (pinfunction "2_2") (pintype "passive"))
      (node (ref "C99") (pin "1") (pinfunction "1_1") (pintype "passive"))
      (node (ref "R66") (pin "2") (pinfunction "2_2") (pintype "passive"))
    )
    (net (code "87") (name "/CB18") (class "Default")
      (node (ref "C100") (pin "1") (pinfunction "1_1") (pintype "passive"))
      (node (ref "C99") (pin "2") (pinfunction "2_2") (pintype "passive"))
      (node (ref "R67") (pin "2") (pinfunction "2_2") (pintype "passive"))
    )
    (net (code "88") (name "/CB19") (class "Default")
      (node (ref "C100") (pin "2") (pinfunction "2_2") (pintype "passive"))
      (node (ref "C101") (pin "1") (pinfunction "1_1") (pintype "passive"))
      (node (ref "R68") (pin "2") (pinfunction "2_2") (pintype "passive"))
    )
    (net (code "89") (name "/CB20") (class "Default")
      (node (ref "C101") (pin "2") (pinfunction "2_2") (pintype "passive"))
      (node (ref "C102") (pin "1") (pinfunction "1_1") (pintype "passive"))
      (node (ref "R69") (pin "2") (pinfunction "2_2") (pintype "passive"))
    )
    (net (code "90") (name "/CB21") (class "Default")
      (node (ref "C102") (pin "2") (pinfunction "2_2") (pintype "passive"))
      (node (ref "C103") (pin "1") (pinfunction "1_1") (pintype "passive"))
      (node (ref "R70") (pin "2") (pinfunction "2_2") (pintype "passive"))
    )
    (net (code "91") (name "/CB22") (class "Default")
      (node (ref "C103") (pin "2") (pinfunction "2_2") (pintype "passive"))
      (node (ref "C104") (pin "1") (pinfunction "1_1") (pintype "passive"))
      (node (ref "R71") (pin "2") (pinfunction "2_2") (pintype "passive"))
    )
    (net (code "92") (name "/CB23") (class "Default")
      (node (ref "C104") (pin "2") (pinfunction "2_2") (pintype "passive"))
      (node (ref "C105") (pin "1") (pinfunction "1_1") (pintype "passive"))
      (node (ref "R72") (pin "2") (pinfunction "2_2") (pintype "passive"))
    )
    (net (code "93") (name "/CB24") (class "Default")
      (node (ref "C105") (pin "2") (pinfunction "2_2") (pintype "passive"))
      (node (ref "C106") (pin "1") (pinfunction "1_1") (pintype "passive"))
      (node (ref "R73") (pin "2") (pinfunction "2_2") (pintype "passive"))
    )
    (net (code "94") (name "/CB25") (class "Default")
      (node (ref "C106") (pin "2") (pinfunction "2_2") (pintype "passive"))
      (node (ref "C107") (pin "1") (pinfunction "1_1") (pintype "passive"))
      (node (ref "R74") (pin "2") (pinfunction "2_2") (pintype "passive"))
    )
    (net (code "95") (name "/CB26") (class "Default")
      (node (ref "C107") (pin "2") (pinfunction "2_2") (pintype "passive"))
      (node (ref "C108") (pin "1") (pinfunction "1_1") (pintype "passive"))
      (node (ref "R75") (pin "2") (pinfunction "2_2") (pintype "passive"))
    )
    (net (code "96") (name "/CB27") (class "Default")
      (node (ref "C108") (pin "2") (pinfunction "2_2") (pintype "passive"))
      (node (ref "C109") (pin "1") (pinfunction "1_1") (pintype "passive"))
      (node (ref "R76") (pin "2") (pinfunction "2_2") (pintype "passive"))
    )
    (net (code "97") (name "/CB28") (class "Default")
      (node (ref "C109") (pin "2") (pinfunction "2_2") (pintype "passive"))
      (node (ref "C110") (pin "1") (pinfunction "1_1") (pintype "passive"))
      (node (ref "R77") (pin "2") (pinfunction "2_2") (pintype "passive"))
    )
    (net (code "98") (name "/CB29") (class "Default")
      (node (ref "C110") (pin "2") (pinfunction "2_2") (pintype "passive"))
      (node (ref "C111") (pin "1") (pinfunction "1_1") (pintype "passive"))
      (node (ref "R78") (pin "2") (pinfunction "2_2") (pintype "passive"))
    )
    (net (code "99") (name "/CB30") (class "Default")
      (node (ref "C111") (pin "2") (pinfunction "2_2") (pintype "passive"))
      (node (ref "C112") (pin "1") (pinfunction "1_1") (pintype "passive"))
      (node (ref "R79") (pin "2") (pinfunction "2_2") (pintype "passive"))
    )
    (net (code "100") (name "/CB31") (class "Default")
      (node (ref "C112") (pin "2") (pinfunction "2_2") (pintype "passive"))
      (node (ref "C113") (pin "1") (pinfunction "1_1") (pintype "passive"))
      (node (ref "R80") (pin "2") (pinfunction "2_2") (pintype "passive"))
    )
    (net (code "101") (name "/CB32") (class "Default")
      (node (ref "C113") (pin "2") (pinfunction "2_2") (pintype "passive"))
      (node (ref "C131") (pin "1") (pinfunction "1_1") (pintype "passive"))
      (node (ref "R81") (pin "2") (pinfunction "2_2") (pintype "passive"))
    )
    (net (code "102") (name "/VC0") (class "Default")
      (node (ref "C81") (pin "1") (pinfunction "1_1") (pintype "passive"))
      (node (ref "C82") (pin "1") (pinfunction "1_1") (pintype "passive"))
      (node (ref "R49") (pin "2") (pinfunction "2_2") (pintype "passive"))
    )
    (net (code "103") (name "/VC1") (class "Default")
      (node (ref "C82") (pin "2") (pinfunction "2_2") (pintype "passive"))
      (node (ref "C83") (pin "1") (pinfunction "1_1") (pintype "passive"))
      (node (ref "R50") (pin "2") (pinfunction "2_2") (pintype "passive"))
    )
    (net (code "104") (name "/VC2") (class "Default")
      (node (ref "C83") (pin "2") (pinfunction "2_2") (pintype "passive"))
      (node (ref "C84") (pin "1") (pinfunction "1_1") (pintype "passive"))
      (node (ref "R51") (pin "2") (pinfunction "2_2") (pintype "passive"))
    )
    (net (code "105") (name "/VC3") (class "Default")
      (node (ref "C84") (pin "2") (pinfunction "2_2") (pintype "passive"))
      (node (ref "C85") (pin "1") (pinfunction "1_1") (pintype "passive"))
      (node (ref "R52") (pin "2") (pinfunction "2_2") (pintype "passive"))
    )
    (net (code "106") (name "/VC4") (class "Default")
      (node (ref "C85") (pin "2") (pinfunction "2_2") (pintype "passive"))
      (node (ref "C86") (pin "1") (pinfunction "1_1") (pintype "passive"))
      (node (ref "R53") (pin "2") (pinfunction "2_2") (pintype "passive"))
    )
    (net (code "107") (name "/VC5") (class "Default")
      (node (ref "C86") (pin "2") (pinfunction "2_2") (pintype "passive"))
      (node (ref "C87") (pin "1") (pinfunction "1_1") (pintype "passive"))
      (node (ref "R54") (pin "2") (pinfunction "2_2") (pintype "passive"))
    )
    (net (code "108") (name "/VC6") (class "Default")
      (node (ref "C87") (pin "2") (pinfunction "2_2") (pintype "passive"))
      (node (ref "C88") (pin "1") (pinfunction "1_1") (pintype "passive"))
      (node (ref "R55") (pin "2") (pinfunction "2_2") (pintype "passive"))
    )
    (net (code "109") (name "/VC7") (class "Default")
      (node (ref "C88") (pin "2") (pinfunction "2_2") (pintype "passive"))
      (node (ref "C89") (pin "1") (pinfunction "1_1") (pintype "passive"))
      (node (ref "R56") (pin "2") (pinfunction "2_2") (pintype "passive"))
    )
    (net (code "110") (name "/VC8") (class "Default")
      (node (ref "C89") (pin "2") (pinfunction "2_2") (pintype "passive"))
      (node (ref "C90") (pin "1") (pinfunction "1_1") (pintype "passive"))
      (node (ref "R57") (pin "2") (pinfunction "2_2") (pintype "passive"))
    )
    (net (code "111") (name "/VC9") (class "Default")
      (node (ref "C90") (pin "2") (pinfunction "2_2") (pintype "passive"))
      (node (ref "C91") (pin "1") (pinfunction "1_1") (pintype "passive"))
      (node (ref "R58") (pin "2") (pinfunction "2_2") (pintype "passive"))
    )
    (net (code "112") (name "/VC10") (class "Default")
      (node (ref "C91") (pin "2") (pinfunction "2_2") (pintype "passive"))
      (node (ref "C92") (pin "1") (pinfunction "1_1") (pintype "passive"))
      (node (ref "R59") (pin "2") (pinfunction "2_2") (pintype "passive"))
    )
    (net (code "113") (name "/VC11") (class "Default")
      (node (ref "C92") (pin "2") (pinfunction "2_2") (pintype "passive"))
      (node (ref "C93") (pin "1") (pinfunction "1_1") (pintype "passive"))
      (node (ref "R60") (pin "2") (pinfunction "2_2") (pintype "passive"))
    )
    (net (code "114") (name "/VC12") (class "Default")
      (node (ref "C93") (pin "2") (pinfunction "2_2") (pintype "passive"))
      (node (ref "C94") (pin "1") (pinfunction "1_1") (pintype "passive"))
      (node (ref "R61") (pin "2") (pinfunction "2_2") (pintype "passive"))
    )
    (net (code "115") (name "/VC13") (class "Default")
      (node (ref "C94") (pin "2") (pinfunction "2_2") (pintype "passive"))
      (node (ref "C95") (pin "1") (pinfunction "1_1") (pintype "passive"))
      (node (ref "R62") (pin "2") (pinfunction "2_2") (pintype "passive"))
    )
    (net (code "116") (name "/VC14") (class "Default")
      (node (ref "C95") (pin "2") (pinfunction "2_2") (pintype "passive"))
      (node (ref "C96") (pin "1") (pinfunction "1_1") (pintype "passive"))
      (node (ref "R63") (pin "2") (pinfunction "2_2") (pintype "passive"))
    )
    (net (code "117") (name "/VC15") (class "Default")
      (node (ref "C96") (pin "2") (pinfunction "2_2") (pintype "passive"))
      (node (ref "C97") (pin "1") (pinfunction "1_1") (pintype "passive"))
      (node (ref "R64") (pin "2") (pinfunction "2_2") (pintype "passive"))
    )
    (net (code "118") (name "/VC16") (class "Default")
      (node (ref "C65") (pin "1") (pinfunction "1_1") (pintype "passive"))
      (node (ref "C97") (pin "2") (pinfunction "2_2") (pintype "passive"))
      (node (ref "R65") (pin "2") (pinfunction "2_2") (pintype "passive"))
    )
    (net (code "119") (name "/VC17") (class "Default")
      (node (ref "C65") (pin "2") (pinfunction "2_2") (pintype "passive"))
      (node (ref "C66") (pin "1") (pinfunction "1_1") (pintype "passive"))
      (node (ref "R32") (pin "2") (pinfunction "2_2") (pintype "passive"))
    )
    (net (code "120") (name "/VC18") (class "Default")
      (node (ref "C66") (pin "2") (pinfunction "2_2") (pintype "passive"))
      (node (ref "C67") (pin "1") (pinfunction "1_1") (pintype "passive"))
      (node (ref "R33") (pin "2") (pinfunction "2_2") (pintype "passive"))
    )
    (net (code "121") (name "/VC19") (class "Default")
      (node (ref "C67") (pin "2") (pinfunction "2_2") (pintype "passive"))
      (node (ref "C68") (pin "1") (pinfunction "1_1") (pintype "passive"))
      (node (ref "R34") (pin "2") (pinfunction "2_2") (pintype "passive"))
    )
    (net (code "122") (name "/VC20") (class "Default")
      (node (ref "C68") (pin "2") (pinfunction "2_2") (pintype "passive"))
      (node (ref "C69") (pin "1") (pinfunction "1_1") (pintype "passive"))
      (node (ref "R35") (pin "2") (pinfunction "2_2") (pintype "passive"))
    )
    (net (code "123") (name "/VC21") (class "Default")
      (node (ref "C69") (pin "2") (pinfunction "2_2") (pintype "passive"))
      (node (ref "C70") (pin "1") (pinfunction "1_1") (pintype "passive"))
      (node (ref "R36") (pin "2") (pinfunction "2_2") (pintype "passive"))
    )
    (net (code "124") (name "/VC22") (class "Default")
      (node (ref "C70") (pin "2") (pinfunction "2_2") (pintype "passive"))
      (node (ref "C71") (pin "1") (pinfunction "1_1") (pintype "passive"))
      (node (ref "R37") (pin "2") (pinfunction "2_2") (pintype "passive"))
    )
    (net (code "125") (name "/VC23") (class "Default")
      (node (ref "C71") (pin "2") (pinfunction "2_2") (pintype "passive"))
      (node (ref "C72") (pin "1") (pinfunction "1_1") (pintype "passive"))
      (node (ref "R38") (pin "2") (pinfunction "2_2") (pintype "passive"))
    )
    (net (code "126") (name "/VC24") (class "Default")
      (node (ref "C72") (pin "2") (pinfunction "2_2") (pintype "passive"))
      (node (ref "C73") (pin "1") (pinfunction "1_1") (pintype "passive"))
      (node (ref "R39") (pin "2") (pinfunction "2_2") (pintype "passive"))
    )
    (net (code "127") (name "/VC25") (class "Default")
      (node (ref "C73") (pin "2") (pinfunction "2_2") (pintype "passive"))
      (node (ref "C74") (pin "1") (pinfunction "1_1") (pintype "passive"))
      (node (ref "R40") (pin "2") (pinfunction "2_2") (pintype "passive"))
    )
    (net (code "128") (name "/VC26") (class "Default")
      (node (ref "C74") (pin "2") (pinfunction "2_2") (pintype "passive"))
      (node (ref "C75") (pin "1") (pinfunction "1_1") (pintype "passive"))
      (node (ref "R41") (pin "2") (pinfunction "2_2") (pintype "passive"))
    )
    (net (code "129") (name "/VC27") (class "Default")
      (node (ref "C75") (pin "2") (pinfunction "2_2") (pintype "passive"))
      (node (ref "C76") (pin "1") (pinfunction "1_1") (pintype "passive"))
      (node (ref "R42") (pin "2") (pinfunction "2_2") (pintype "passive"))
    )
    (net (code "130") (name "/VC28") (class "Default")
      (node (ref "C76") (pin "2") (pinfunction "2_2") (pintype "passive"))
      (node (ref "C77") (pin "1") (pinfunction "1_1") (pintype "passive"))
      (node (ref "R43") (pin "2") (pinfunction "2_2") (pintype "passive"))
    )
    (net (code "131") (name "/VC29") (class "Default")
      (node (ref "C77") (pin "2") (pinfunction "2_2") (pintype "passive"))
      (node (ref "C78") (pin "1") (pinfunction "1_1") (pintype "passive"))
      (node (ref "R44") (pin "2") (pinfunction "2_2") (pintype "passive"))
    )
    (net (code "132") (name "/VC30") (class "Default")
      (node (ref "C78") (pin "2") (pinfunction "2_2") (pintype "passive"))
      (node (ref "C79") (pin "1") (pinfunction "1_1") (pintype "passive"))
      (node (ref "R45") (pin "2") (pinfunction "2_2") (pintype "passive"))
    )
    (net (code "133") (name "/VC31") (class "Default")
      (node (ref "C79") (pin "2") (pinfunction "2_2") (pintype "passive"))
      (node (ref "C80") (pin "1") (pinfunction "1_1") (pintype "passive"))
      (node (ref "R46") (pin "2") (pinfunction "2_2") (pintype "passive"))
    )
    (net (code "134") (name "/VC32") (class "Default")
      (node (ref "C80") (pin "2") (pinfunction "2_2") (pintype "passive"))
      (node (ref "R47") (pin "2") (pinfunction "2_2") (pintype "passive"))
    )
    (net (code "135") (name "BAT_GND") (class "Default")
      (node (ref "C114") (pin "1") (pinfunction "1_1") (pintype "passive"))
      (node (ref "C81") (pin "2") (pinfunction "2_2") (pintype "passive"))
      (node (ref "R48") (pin "1") (pinfunction "1_1") (pintype "passive"))
    )
    (net (code "136") (name "BQ1_GND") (class "Default")
      (node (ref "C134") (pin "1") (pinfunction "1_1") (pintype "passive"))
    )
    (net (code "137") (name "BQ2_GND") (class "Default")
      (node (ref "C133") (pin "1") (pinfunction "1_1") (pintype "passive"))
    )
  )
)
